# MOTOR_DRIVER_DRV10866.net
KiCad netlist of a schematic drawn in Altium Designer
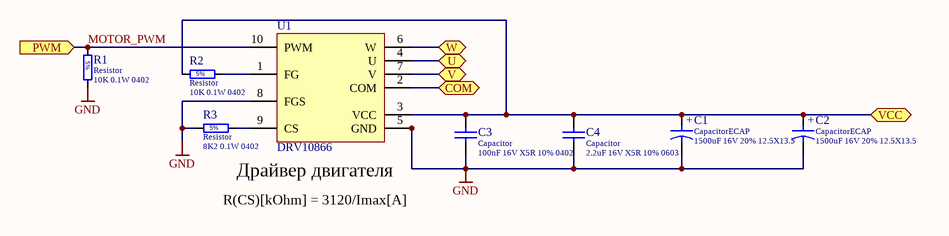
[diagram p0: MOTOR_DRIVER_DRV10866.SchDoc]

(export (version "E")
  (design (tool "Eeschema 10.0.6"))
  (components
    (comp (ref "C1")
      (value "CapacitorECAP")
      (footprint "12.5X13.5")
      (description "Aluminium polarized cap")
      (fields
        (field (name "VOLTAGE") "16V")
        (field (name "TOLERANCE") "20%")
        (field (name "ALTIUM_VALUE") "1500uF 16V 20% ")
      )
      (libsource (lib "Passive") (part "CapacitorECAP"))
    )
    (comp (ref "C2")
      (value "CapacitorECAP")
      (footprint "12.5X13.5")
      (description "Aluminium polarized cap")
      (fields
        (field (name "VOLTAGE") "16V")
        (field (name "TOLERANCE") "20%")
        (field (name "ALTIUM_VALUE") "1500uF 16V 20% ")
      )
      (libsource (lib "Passive") (part "CapacitorECAP"))
    )
    (comp (ref "C3")
      (value "Capacitor")
      (footprint "CAP_SMD:0402")
      (description "Ceramic capacitor")
      (fields
        (field (name "VOLTAGE") "16V")
        (field (name "TOLERANCE") "10%")
        (field (name "ALTIUM_VALUE") "100nF 16V X5R 10% ")
      )
      (libsource (lib "Passive") (part "Capacitor ceramic"))
    )
    (comp (ref "C4")
      (value "Capacitor")
      (footprint "CAP_SMD:0603")
      (description "Ceramic capacitor")
      (fields
        (field (name "VOLTAGE") "16V")
        (field (name "TOLERANCE") "10%")
        (field (name "ALTIUM_VALUE") "2.2uF 16V X5R 10% ")
      )
      (libsource (lib "Passive") (part "Capacitor ceramic"))
    )
    (comp (ref "R1")
      (value "Resistor")
      (footprint "RES_SMD:0402")
      (description "Thin Film Chip Resistor")
      (fields
        (field (name "POWER") "0.1W")
        (field (name "TOLERANCE") "5%")
        (field (name "ALTIUM_VALUE") "10K 0.1W ")
      )
      (libsource (lib "Passive") (part "Resistor"))
    )
    (comp (ref "R2")
      (value "Resistor")
      (footprint "RES_SMD:0402")
      (description "Thin Film Chip Resistor")
      (fields
        (field (name "POWER") "0.1W")
        (field (name "TOLERANCE") "5%")
        (field (name "ALTIUM_VALUE") "10K 0.1W ")
      )
      (libsource (lib "Passive") (part "Resistor"))
    )
    (comp (ref "R3")
      (value "Resistor")
      (footprint "RES_SMD:0402")
      (description "Thin Film Chip Resistor")
      (fields
        (field (name "POWER") "0.1W")
        (field (name "TOLERANCE") "5%")
        (field (name "ALTIUM_VALUE") "8K2 0.1W ")
      )
      (libsource (lib "Passive") (part "Resistor"))
    )
    (comp (ref "U1")
      (value "DRV10866")
      (footprint "SON:SON-10-0.5_3x3")
      (description "5-V, 3-Phase, Sensorless BLDC Motor Driver")
      (libsource (lib "IC_MOTOR_CTRL") (part "DRV10866"))
    )
  )
  (nets
    (net (code "1") (name "/COM") (class "Default")
      (node (ref "U1") (pin "2") (pinfunction "COM_2") (pintype "passive"))
    )
    (net (code "2") (name "/MOTOR_PWM") (class "Default")
      (node (ref "R1") (pin "1") (pinfunction "1_1") (pintype "passive"))
      (node (ref "U1") (pin "10") (pinfunction "PWM_10") (pintype "passive"))
    )
    (net (code "3") (name "/U") (class "Default")
      (node (ref "U1") (pin "4") (pinfunction "U_4") (pintype "passive"))
    )
    (net (code "4") (name "/V") (class "Default")
      (node (ref "U1") (pin "7") (pinfunction "V_7") (pintype "passive"))
    )
    (net (code "5") (name "/VCC") (class "Default")
      (node (ref "C1") (pin "1") (pinfunction "1_1") (pintype "passive"))
      (node (ref "C2") (pin "1") (pinfunction "1_1") (pintype "passive"))
      (node (ref "C3") (pin "2") (pinfunction "2_2") (pintype "passive"))
      (node (ref "C4") (pin "2") (pinfunction "2_2") (pintype "passive"))
      (node (ref "R2") (pin "1") (pinfunction "1_1") (pintype "passive"))
      (node (ref "U1") (pin "3") (pinfunction "VCC_3") (pintype "passive"))
    )
    (net (code "6") (name "/W") (class "Default")
      (node (ref "U1") (pin "6") (pinfunction "W_6") (pintype "passive"))
    )
    (net (code "7") (name "GND") (class "Default")
      (node (ref "C1") (pin "2") (pinfunction "2_2") (pintype "passive"))
      (node (ref "C2") (pin "2") (pinfunction "2_2") (pintype "passive"))
      (node (ref "C3") (pin "1") (pinfunction "1_1") (pintype "passive"))
      (node (ref "C4") (pin "1") (pinfunction "1_1") (pintype "passive"))
      (node (ref "R1") (pin "2") (pinfunction "2_2") (pintype "passive"))
      (node (ref "R3") (pin "1") (pinfunction "1_1") (pintype "passive"))
      (node (ref "U1") (pin "11") (pinfunction "GND_11") (pintype "passive"))
      (node (ref "U1") (pin "5") (pinfunction "GND_5") (pintype "passive"))
      (node (ref "U1") (pin "8") (pinfunction "FGS_8") (pintype "passive"))
    )
    (net (code "8") (name "Net-(U1-CS)") (class "Default")
      (node (ref "R3") (pin "2") (pinfunction "2_2") (pintype "passive"))
      (node (ref "U1") (pin "9") (pinfunction "CS_9") (pintype "passive"))
    )
    (net (code "9") (name "Net-(U1-FG)") (class "Default")
      (node (ref "R2") (pin "2") (pinfunction "2_2") (pintype "passive"))
      (node (ref "U1") (pin "1") (pinfunction "FG_1") (pintype "passive"))
    )
  )
)
